# in_out.net
KiCad netlist of a schematic drawn in Altium Designer
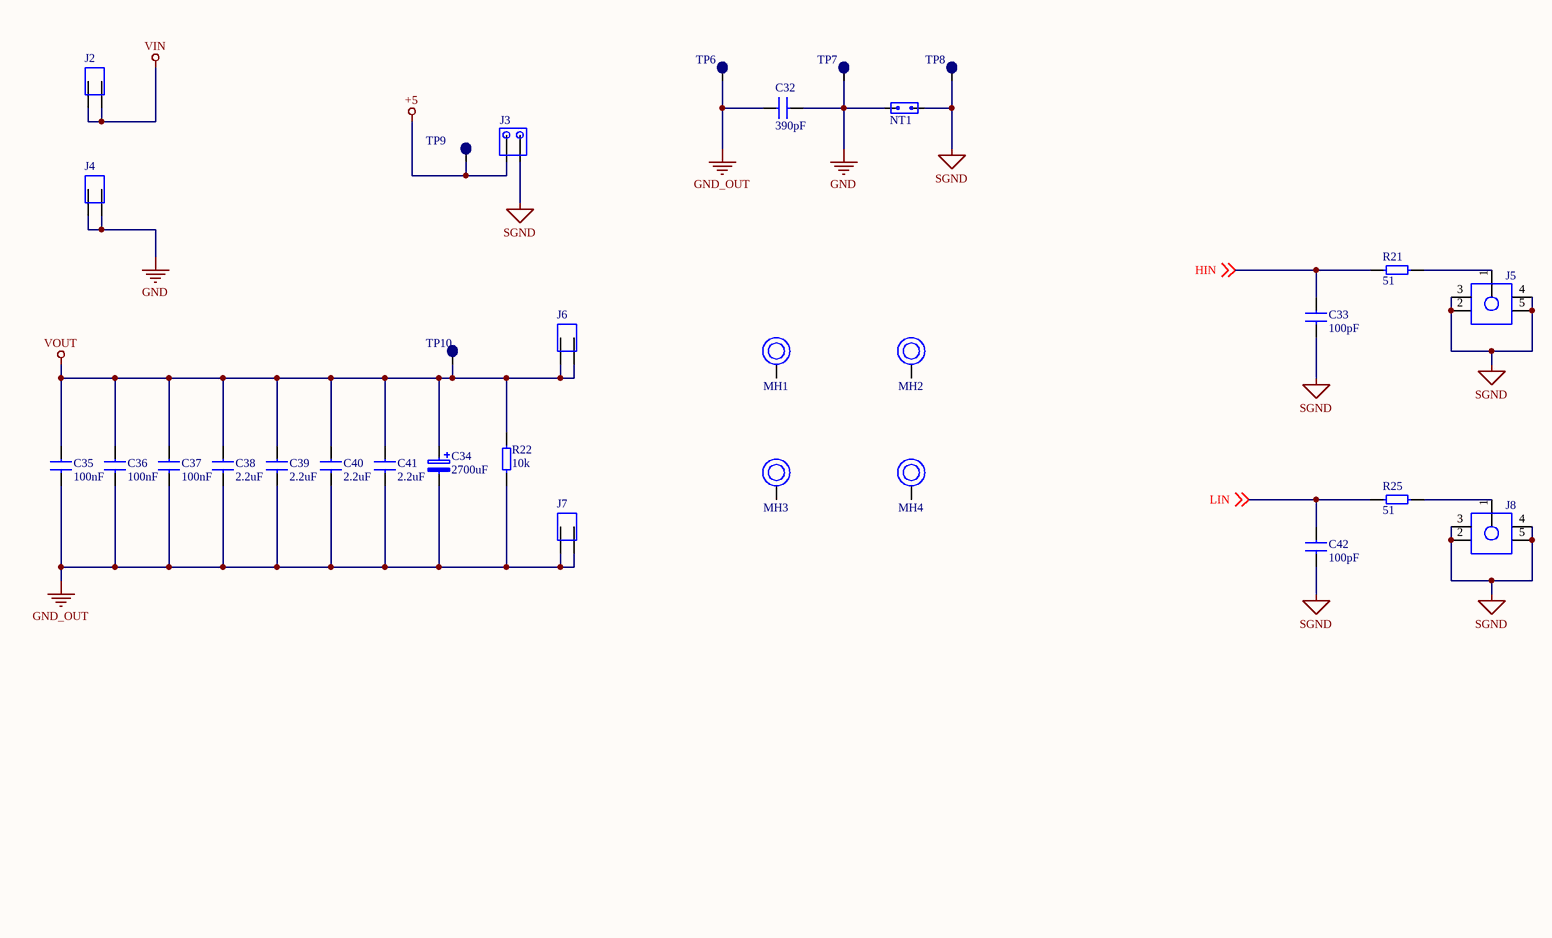
[diagram p0: in_out.SchDoc]

(export (version "E")
  (design (tool "Eeschema 10.0.6"))
  (components
    (comp (ref "C32")
      (value "390pF")
      (footprint "KN_ECART:Capacitor_1812")
      (description "Capacitor - Standard SMD")
      (fields (field (name "VOLTAGE") "2kV") (field (name "MPN") "1812B391K202CT"))
      (libsource (lib "KN_ECART") (part "Capacitor_1812"))
    )
    (comp (ref "C33")
      (value "100pF")
      (footprint "KN_ECART:Capacitor_0805")
      (description "Capacitor - Standard SMD")
      (fields (field (name "VOLTAGE") "12V"))
      (libsource (lib "KN_ECART") (part "Capacitor_0805"))
    )
    (comp (ref "C34")
      (value "2700uF")
      (footprint "Capacitor_Electrolytic_Vib_Res")
      (description "Capacitor - Electrolytic  SMD")
      (fields (field (name "VOLTAGE") "35V"))
      (libsource (lib "KN_ECART") (part "Capacitor_Electrolytic_Vib_Res"))
    )
    (comp (ref "C35")
      (value "100nF")
      (footprint "Magisterium:Capacitor_0805")
      (description "Capacitor - Standard SMD")
      (fields (field (name "VOLTAGE") "50V") (field (name "MPN") "CL21B104KBCNNND"))
      (libsource (lib "Magisterium") (part "Capacitor_0805"))
    )
    (comp (ref "C36")
      (value "100nF")
      (footprint "Magisterium:Capacitor_0805")
      (description "Capacitor - Standard SMD")
      (fields (field (name "VOLTAGE") "50V") (field (name "MPN") "CL21B104KBCNNND"))
      (libsource (lib "Magisterium") (part "Capacitor_0805"))
    )
    (comp (ref "C37")
      (value "100nF")
      (footprint "Magisterium:Capacitor_0805")
      (description "Capacitor - Standard SMD")
      (fields (field (name "VOLTAGE") "50V") (field (name "MPN") "CL21B104KBCNNND"))
      (libsource (lib "Magisterium") (part "Capacitor_0805"))
    )
    (comp (ref "C38")
      (value "2.2uF")
      (footprint "KN_ECART:Capcitor_1206")
      (description "Capacitor - Standard SMD")
      (fields (field (name "VOLTAGE") "50V") (field (name "MPN") "CL31B225KBHNFNE"))
      (libsource (lib "KN_ECART") (part "Capacitor_1206"))
    )
    (comp (ref "C39")
      (value "2.2uF")
      (footprint "KN_ECART:Capcitor_1206")
      (description "Capacitor - Standard SMD")
      (fields (field (name "VOLTAGE") "50V") (field (name "MPN") "CL31B225KBHNFNE"))
      (libsource (lib "KN_ECART") (part "Capacitor_1206"))
    )
    (comp (ref "C40")
      (value "2.2uF")
      (footprint "KN_ECART:Capcitor_1206")
      (description "Capacitor - Standard SMD")
      (fields (field (name "VOLTAGE") "50V") (field (name "MPN") "CL31B225KBHNFNE"))
      (libsource (lib "KN_ECART") (part "Capacitor_1206"))
    )
    (comp (ref "C41")
      (value "2.2uF")
      (footprint "KN_ECART:Capcitor_1206")
      (description "Capacitor - Standard SMD")
      (fields (field (name "VOLTAGE") "50V") (field (name "MPN") "CL31B225KBHNFNE"))
      (libsource (lib "KN_ECART") (part "Capacitor_1206"))
    )
    (comp (ref "C42")
      (value "100pF")
      (footprint "KN_ECART:Capacitor_0805")
      (description "Capacitor - Standard SMD")
      (fields (field (name "VOLTAGE") "12V"))
      (libsource (lib "KN_ECART") (part "Capacitor_0805"))
    )
    (comp (ref "J2")
      (value "1289-STR")
      (footprint "KN_ECART:1289STR")
      (description "Connector")
      (fields (field (name "MOUSER PART NUMBER") "534-1289-STR"))
      (libsource (lib "KN_ECART") (part "1289-STR"))
    )
    (comp (ref "J3")
      (value "Connector_3.5mm")
      (footprint "KN_ECART:Connector_3.5")
      (libsource (lib "KN_ECART") (part "Connector_3.5mm"))
    )
    (comp (ref "J4")
      (value "1289-STR")
      (footprint "KN_ECART:1289STR")
      (description "Connector")
      (fields (field (name "MOUSER PART NUMBER") "534-1289-STR"))
      (libsource (lib "KN_ECART") (part "1289-STR"))
    )
    (comp (ref "J5")
      (value "142-0701-301")
      (footprint "1420701301")
      (description "Connector")
      (fields
        (field (name "MOUSER PART NUMBER") "530-142-0701-301")
        (field (name "SOURCE") "KN_ECART.SchLib")
      )
      (libsource (lib "KN_ECART") (part "142-0701-301"))
    )
    (comp (ref "J6")
      (value "1289-STR")
      (footprint "KN_ECART:1289STR")
      (description "Connector")
      (fields (field (name "MOUSER PART NUMBER") "534-1289-STR"))
      (libsource (lib "KN_ECART") (part "1289-STR"))
    )
    (comp (ref "J7")
      (value "1289-STR")
      (footprint "KN_ECART:1289STR")
      (description "Connector")
      (fields (field (name "MOUSER PART NUMBER") "534-1289-STR"))
      (libsource (lib "KN_ECART") (part "1289-STR"))
    )
    (comp (ref "J8")
      (value "142-0701-301")
      (footprint "1420701301")
      (description "Connector")
      (fields
        (field (name "MOUSER PART NUMBER") "530-142-0701-301")
        (field (name "SOURCE") "KN_ECART.SchLib")
      )
      (libsource (lib "KN_ECART") (part "142-0701-301"))
    )
    (comp (ref "MH1")
      (value "Mounting_Hole_M3")
      (footprint "KN_ECART:Mounting_Hole_M3")
      (libsource (lib "KN_ECART") (part "Mounting_Hole_M3"))
    )
    (comp (ref "MH2")
      (value "Mounting_Hole_M3")
      (footprint "KN_ECART:Mounting_Hole_M3")
      (libsource (lib "KN_ECART") (part "Mounting_Hole_M3"))
    )
    (comp (ref "MH3")
      (value "Mounting_Hole_M3")
      (footprint "KN_ECART:Mounting_Hole_M3")
      (libsource (lib "KN_ECART") (part "Mounting_Hole_M3"))
    )
    (comp (ref "MH4")
      (value "Mounting_Hole_M3")
      (footprint "KN_ECART:Mounting_Hole_M3")
      (libsource (lib "KN_ECART") (part "Mounting_Hole_M3"))
    )
    (comp (ref "NT1") (value "Net tie") (footprint "Net tie") (libsource (lib "KN_ECART") (part "Net tie")))
    (comp (ref "R21")
      (value "51")
      (footprint "Resistor_0805")
      (description "Resistor - Standard SMD")
      (libsource (lib "KN_ECART") (part "Resistor_0805"))
    )
    (comp (ref "R22")
      (value "10k")
      (footprint "KN_ECART:Resistor_1206")
      (description "Resistor - Standard SMD")
      (libsource (lib "KN_ECART") (part "Resistor_1206"))
    )
    (comp (ref "R25")
      (value "51")
      (footprint "Resistor_0805")
      (description "Resistor - Standard SMD")
      (libsource (lib "KN_ECART") (part "Resistor_0805"))
    )
    (comp (ref "TP6")
      (value "Test point")
      (footprint "Test point")
      (libsource (lib "KN_ECART") (part "Test point"))
    )
    (comp (ref "TP7")
      (value "Test point")
      (footprint "Test point")
      (libsource (lib "KN_ECART") (part "Test point"))
    )
    (comp (ref "TP8")
      (value "Test point")
      (footprint "Test point")
      (libsource (lib "KN_ECART") (part "Test point"))
    )
    (comp (ref "TP9")
      (value "Test point")
      (footprint "Test point")
      (libsource (lib "KN_ECART") (part "Test point"))
    )
    (comp (ref "TP10")
      (value "Test point")
      (footprint "Test point")
      (libsource (lib "KN_ECART") (part "Test point"))
    )
  )
  (nets
    (net (code "1") (name "+5") (class "Default")
      (node (ref "J3") (pin "2") (pinfunction "2_2") (pintype "passive"))
      (node (ref "TP9") (pin "1") (pintype "passive"))
    )
    (net (code "3") (name "GND") (class "Default")
      (node (ref "C32") (pin "2") (pintype "passive"))
      (node (ref "J4") (pin "1") (pinfunction "1_1") (pintype "passive"))
      (node (ref "J4") (pin "2") (pinfunction "2_2") (pintype "passive"))
      (node (ref "NT1") (pin "1") (pintype "passive"))
      (node (ref "TP7") (pin "1") (pintype "passive"))
    )
    (net (code "4") (name "GND_OUT") (class "Default")
      (node (ref "C32") (pin "1") (pintype "passive"))
      (node (ref "C34") (pin "2") (pintype "passive"))
      (node (ref "C35") (pin "1") (pintype "passive"))
      (node (ref "C36") (pin "1") (pintype "passive"))
      (node (ref "C37") (pin "1") (pintype "passive"))
      (node (ref "C38") (pin "1") (pintype "passive"))
      (node (ref "C39") (pin "1") (pintype "passive"))
      (node (ref "C40") (pin "1") (pintype "passive"))
      (node (ref "C41") (pin "1") (pintype "passive"))
      (node (ref "J7") (pin "1") (pinfunction "1_1") (pintype "passive"))
      (node (ref "J7") (pin "2") (pinfunction "2_2") (pintype "passive"))
      (node (ref "R22") (pin "1") (pintype "passive"))
      (node (ref "TP6") (pin "1") (pintype "passive"))
    )
    (net (code "5") (name "HIN") (class "Default")
      (node (ref "C33") (pin "2") (pintype "passive"))
      (node (ref "R21") (pin "1") (pintype "passive"))
    )
    (net (code "6") (name "LIN") (class "Default")
      (node (ref "C42") (pin "2") (pintype "passive"))
      (node (ref "R25") (pin "1") (pintype "passive"))
    )
    (net (code "7") (name "Net-(J5-Pad1)") (class "Default")
      (node (ref "J5") (pin "1") (pinfunction "1_1") (pintype "passive"))
      (node (ref "R21") (pin "2") (pintype "passive"))
    )
    (net (code "8") (name "Net-(J8-Pad1)") (class "Default")
      (node (ref "J8") (pin "1") (pinfunction "1_1") (pintype "passive"))
      (node (ref "R25") (pin "2") (pintype "passive"))
    )
    (net (code "9") (name "SGND") (class "Default")
      (node (ref "C33") (pin "1") (pintype "passive"))
      (node (ref "C42") (pin "1") (pintype "passive"))
      (node (ref "J3") (pin "1") (pinfunction "1_1") (pintype "passive"))
      (node (ref "J5") (pin "2") (pinfunction "2_2") (pintype "passive"))
      (node (ref "J5") (pin "3") (pinfunction "3_3") (pintype "passive"))
      (node (ref "J5") (pin "4") (pinfunction "4_4") (pintype "passive"))
      (node (ref "J5") (pin "5") (pinfunction "5_5") (pintype "passive"))
      (node (ref "J8") (pin "2") (pinfunction "2_2") (pintype "passive"))
      (node (ref "J8") (pin "3") (pinfunction "3_3") (pintype "passive"))
      (node (ref "J8") (pin "4") (pinfunction "4_4") (pintype "passive"))
      (node (ref "J8") (pin "5") (pinfunction "5_5") (pintype "passive"))
      (node (ref "NT1") (pin "2") (pintype "passive"))
      (node (ref "TP8") (pin "1") (pintype "passive"))
    )
    (net (code "10") (name "VIN") (class "Default")
      (node (ref "J2") (pin "1") (pinfunction "1_1") (pintype "passive"))
      (node (ref "J2") (pin "2") (pinfunction "2_2") (pintype "passive"))
    )
    (net (code "11") (name "VOUT") (class "Default")
      (node (ref "C34") (pin "1") (pintype "passive"))
      (node (ref "C35") (pin "2") (pintype "passive"))
      (node (ref "C36") (pin "2") (pintype "passive"))
      (node (ref "C37") (pin "2") (pintype "passive"))
      (node (ref "C38") (pin "2") (pintype "passive"))
      (node (ref "C39") (pin "2") (pintype "passive"))
      (node (ref "C40") (pin "2") (pintype "passive"))
      (node (ref "C41") (pin "2") (pintype "passive"))
      (node (ref "J6") (pin "1") (pinfunction "1_1") (pintype "passive"))
      (node (ref "J6") (pin "2") (pinfunction "2_2") (pintype "passive"))
      (node (ref "R22") (pin "2") (pintype "passive"))
      (node (ref "TP10") (pin "1") (pintype "passive"))
    )
    (net (code "12") (name "unconnected-(MH1-Pad1)") (class "Default")
      (node (ref "MH1") (pin "1") (pintype "passive"))
    )
    (net (code "13") (name "unconnected-(MH2-Pad1)") (class "Default")
      (node (ref "MH2") (pin "1") (pintype "passive"))
    )
    (net (code "14") (name "unconnected-(MH3-Pad1)") (class "Default")
      (node (ref "MH3") (pin "1") (pintype "passive"))
    )
    (net (code "15") (name "unconnected-(MH4-Pad1)") (class "Default")
      (node (ref "MH4") (pin "1") (pintype "passive"))
    )
  )
)
